# I2C-Temp-sensor.net
KiCad netlist of a schematic drawn in Altium Designer
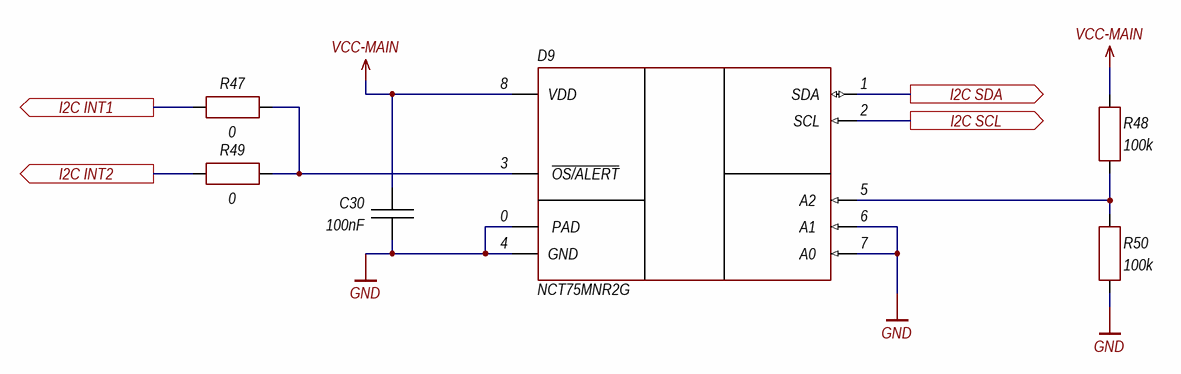
[diagram p0: I2C-Temp-sensor.SchDoc]

(export (version "E")
  (design (tool "Eeschema 10.0.6"))
  (components
    (comp (ref "C30") (value "100nF") (footprint "CH0402C") (libsource (lib "Discrete") (part "Capacitor")))
    (comp (ref "D9")
      (value "NCT75MNR2G")
      (footprint "8-DFN (2x2 mm, 0.5mm pitch, EP)")
      (description "Temperature Sensor, I2C")
      (fields (field (name "MANUFACTURER") "onsemi"))
      (libsource (lib "Digital") (part "NCT75MNR2G"))
    )
    (comp (ref "R47") (value "0") (footprint "CH0402R") (libsource (lib "Discrete") (part "Resistor")))
    (comp (ref "R48") (value "100k") (footprint "CH0402R") (libsource (lib "") (part "Resistor_1")))
    (comp (ref "R49") (value "0") (footprint "CH0402R") (libsource (lib "Discrete") (part "Resistor")))
    (comp (ref "R50") (value "100k") (footprint "CH0402R") (libsource (lib "") (part "Resistor_1")))
  )
  (nets
    (net (code "1") (name "/I2C INT1") (class "Default")
      (node (ref "R47") (pin "1") (pinfunction "1_1") (pintype "passive"))
    )
    (net (code "2") (name "/I2C INT2") (class "Default")
      (node (ref "R49") (pin "1") (pinfunction "1_1") (pintype "passive"))
    )
    (net (code "3") (name "/I2C SCL") (class "Default")
      (node (ref "D9") (pin "2") (pinfunction "SCL_2") (pintype "input"))
    )
    (net (code "4") (name "/I2C SDA") (class "Default")
      (node (ref "D9") (pin "1") (pinfunction "SDA_1") (pintype "bidirectional"))
    )
    (net (code "5") (name "GND") (class "Default")
      (node (ref "C30") (pin "1") (pinfunction "1_1") (pintype "passive"))
      (node (ref "D9") (pin "0") (pinfunction "PAD_0") (pintype "power_in"))
      (node (ref "D9") (pin "4") (pinfunction "GND_4") (pintype "power_in"))
      (node (ref "D9") (pin "6") (pinfunction "A1_6") (pintype "input"))
      (node (ref "D9") (pin "7") (pinfunction "A0_7") (pintype "input"))
      (node (ref "R50") (pin "1") (pinfunction "1_1") (pintype "passive"))
    )
    (net (code "6") (name "Net-(D9-A2)") (class "Default")
      (node (ref "D9") (pin "5") (pinfunction "A2_5") (pintype "input"))
      (node (ref "R48") (pin "1") (pinfunction "1_1") (pintype "passive"))
      (node (ref "R50") (pin "2") (pinfunction "2_2") (pintype "passive"))
    )
    (net (code "7") (name "Net-(D9-~{OS{slash}ALERT})") (class "Default")
      (node (ref "D9") (pin "3") (pinfunction "~{OS/ALERT}_3") (pintype "open_collector"))
      (node (ref "R47") (pin "2") (pinfunction "2_2") (pintype "passive"))
      (node (ref "R49") (pin "2") (pinfunction "2_2") (pintype "passive"))
    )
    (net (code "8") (name "VCC-MAIN") (class "Default")
      (node (ref "C30") (pin "2") (pinfunction "2_2") (pintype "passive"))
      (node (ref "D9") (pin "8") (pinfunction "VDD_8") (pintype "power_in"))
      (node (ref "R48") (pin "2") (pinfunction "2_2") (pintype "passive"))
    )
  )
)
